# 12_IO.net
KiCad netlist of a schematic drawn in Altium Designer
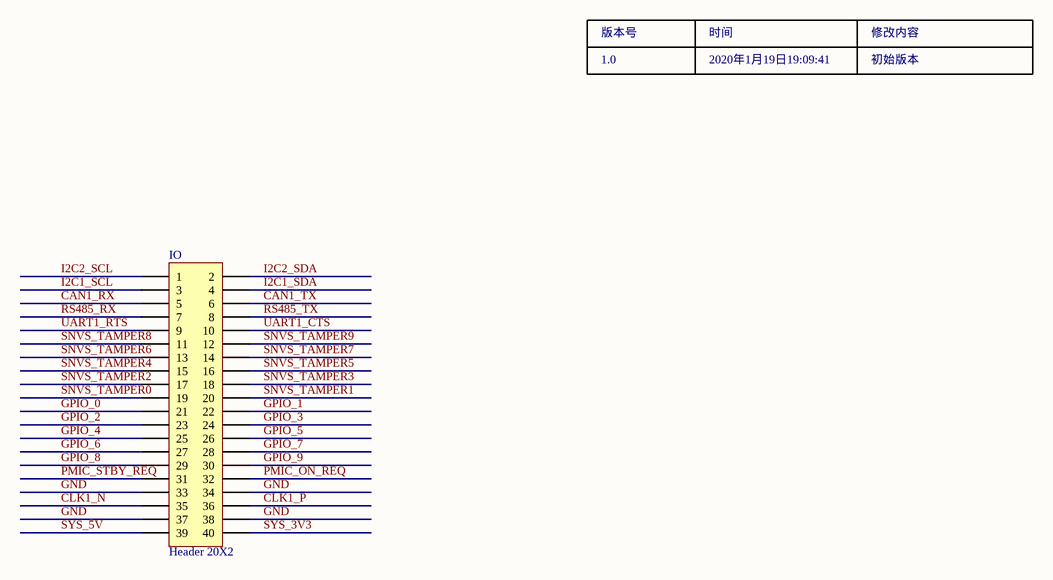
[diagram p0: 12_IO.SchDoc]

(export (version "E")
  (design (tool "Eeschema 10.0.6"))
  (components
    (comp (ref "IO")
      (value "Header 20X2")
      (footprint "HDR2X20")
      (description "Header, 20-Pin, Dual row")
      (fields (field (name "PUBLISHER") "Altium Limited"))
      (libsource (lib "Miscellaneous Connectors") (part "Header 20X2"))
    )
  )
  (nets
    (net (code "1") (name "/CAN1_RX") (class "Default")
      (node (ref "IO") (pin "5") (pinfunction "5_5") (pintype "passive"))
    )
    (net (code "2") (name "/CAN1_TX") (class "Default")
      (node (ref "IO") (pin "6") (pinfunction "6_6") (pintype "passive"))
    )
    (net (code "3") (name "/CLK1_N") (class "Default")
      (node (ref "IO") (pin "35") (pinfunction "35_35") (pintype "passive"))
    )
    (net (code "4") (name "/CLK1_P") (class "Default")
      (node (ref "IO") (pin "36") (pinfunction "36_36") (pintype "passive"))
    )
    (net (code "5") (name "/GND") (class "Default")
      (node (ref "IO") (pin "33") (pinfunction "33_33") (pintype "passive"))
      (node (ref "IO") (pin "34") (pinfunction "34_34") (pintype "passive"))
      (node (ref "IO") (pin "37") (pinfunction "37_37") (pintype "passive"))
      (node (ref "IO") (pin "38") (pinfunction "38_38") (pintype "passive"))
    )
    (net (code "6") (name "/GPIO_0") (class "Default")
      (node (ref "IO") (pin "21") (pinfunction "21_21") (pintype "passive"))
    )
    (net (code "7") (name "/GPIO_1") (class "Default")
      (node (ref "IO") (pin "22") (pinfunction "22_22") (pintype "passive"))
    )
    (net (code "8") (name "/GPIO_2") (class "Default")
      (node (ref "IO") (pin "23") (pinfunction "23_23") (pintype "passive"))
    )
    (net (code "9") (name "/GPIO_3") (class "Default")
      (node (ref "IO") (pin "24") (pinfunction "24_24") (pintype "passive"))
    )
    (net (code "10") (name "/GPIO_4") (class "Default")
      (node (ref "IO") (pin "25") (pinfunction "25_25") (pintype "passive"))
    )
    (net (code "11") (name "/GPIO_5") (class "Default")
      (node (ref "IO") (pin "26") (pinfunction "26_26") (pintype "passive"))
    )
    (net (code "12") (name "/GPIO_6") (class "Default")
      (node (ref "IO") (pin "27") (pinfunction "27_27") (pintype "passive"))
    )
    (net (code "13") (name "/GPIO_7") (class "Default")
      (node (ref "IO") (pin "28") (pinfunction "28_28") (pintype "passive"))
    )
    (net (code "14") (name "/GPIO_8") (class "Default")
      (node (ref "IO") (pin "29") (pinfunction "29_29") (pintype "passive"))
    )
    (net (code "15") (name "/GPIO_9") (class "Default")
      (node (ref "IO") (pin "30") (pinfunction "30_30") (pintype "passive"))
    )
    (net (code "16") (name "/I2C1_SCL") (class "Default")
      (node (ref "IO") (pin "3") (pinfunction "3_3") (pintype "passive"))
    )
    (net (code "17") (name "/I2C1_SDA") (class "Default")
      (node (ref "IO") (pin "4") (pinfunction "4_4") (pintype "passive"))
    )
    (net (code "18") (name "/I2C2_SCL") (class "Default")
      (node (ref "IO") (pin "1") (pinfunction "1_1") (pintype "passive"))
    )
    (net (code "19") (name "/I2C2_SDA") (class "Default")
      (node (ref "IO") (pin "2") (pinfunction "2_2") (pintype "passive"))
    )
    (net (code "20") (name "/PMIC_ON_REQ") (class "Default")
      (node (ref "IO") (pin "32") (pinfunction "32_32") (pintype "passive"))
    )
    (net (code "21") (name "/PMIC_STBY_REQ") (class "Default")
      (node (ref "IO") (pin "31") (pinfunction "31_31") (pintype "passive"))
    )
    (net (code "22") (name "/RS485_RX") (class "Default")
      (node (ref "IO") (pin "7") (pinfunction "7_7") (pintype "passive"))
    )
    (net (code "23") (name "/RS485_TX") (class "Default")
      (node (ref "IO") (pin "8") (pinfunction "8_8") (pintype "passive"))
    )
    (net (code "24") (name "/SNVS_TAMPER0") (class "Default")
      (node (ref "IO") (pin "19") (pinfunction "19_19") (pintype "passive"))
    )
    (net (code "25") (name "/SNVS_TAMPER1") (class "Default")
      (node (ref "IO") (pin "20") (pinfunction "20_20") (pintype "passive"))
    )
    (net (code "26") (name "/SNVS_TAMPER2") (class "Default")
      (node (ref "IO") (pin "17") (pinfunction "17_17") (pintype "passive"))
    )
    (net (code "27") (name "/SNVS_TAMPER3") (class "Default")
      (node (ref "IO") (pin "18") (pinfunction "18_18") (pintype "passive"))
    )
    (net (code "28") (name "/SNVS_TAMPER4") (class "Default")
      (node (ref "IO") (pin "15") (pinfunction "15_15") (pintype "passive"))
    )
    (net (code "29") (name "/SNVS_TAMPER5") (class "Default")
      (node (ref "IO") (pin "16") (pinfunction "16_16") (pintype "passive"))
    )
    (net (code "30") (name "/SNVS_TAMPER6") (class "Default")
      (node (ref "IO") (pin "13") (pinfunction "13_13") (pintype "passive"))
    )
    (net (code "31") (name "/SNVS_TAMPER7") (class "Default")
      (node (ref "IO") (pin "14") (pinfunction "14_14") (pintype "passive"))
    )
    (net (code "32") (name "/SNVS_TAMPER8") (class "Default")
      (node (ref "IO") (pin "11") (pinfunction "11_11") (pintype "passive"))
    )
    (net (code "33") (name "/SNVS_TAMPER9") (class "Default")
      (node (ref "IO") (pin "12") (pinfunction "12_12") (pintype "passive"))
    )
    (net (code "34") (name "/SYS_3V3") (class "Default")
      (node (ref "IO") (pin "40") (pinfunction "40_40") (pintype "passive"))
    )
    (net (code "35") (name "/SYS_5V") (class "Default")
      (node (ref "IO") (pin "39") (pinfunction "39_39") (pintype "passive"))
    )
    (net (code "36") (name "/UART1_CTS") (class "Default")
      (node (ref "IO") (pin "10") (pinfunction "10_10") (pintype "passive"))
    )
    (net (code "37") (name "/UART1_RTS") (class "Default")
      (node (ref "IO") (pin "9") (pinfunction "9_9") (pintype "passive"))
    )
  )
)
